# PROC106B_AOP_PWR.net
KiCad netlist of a schematic drawn in Altium Designer
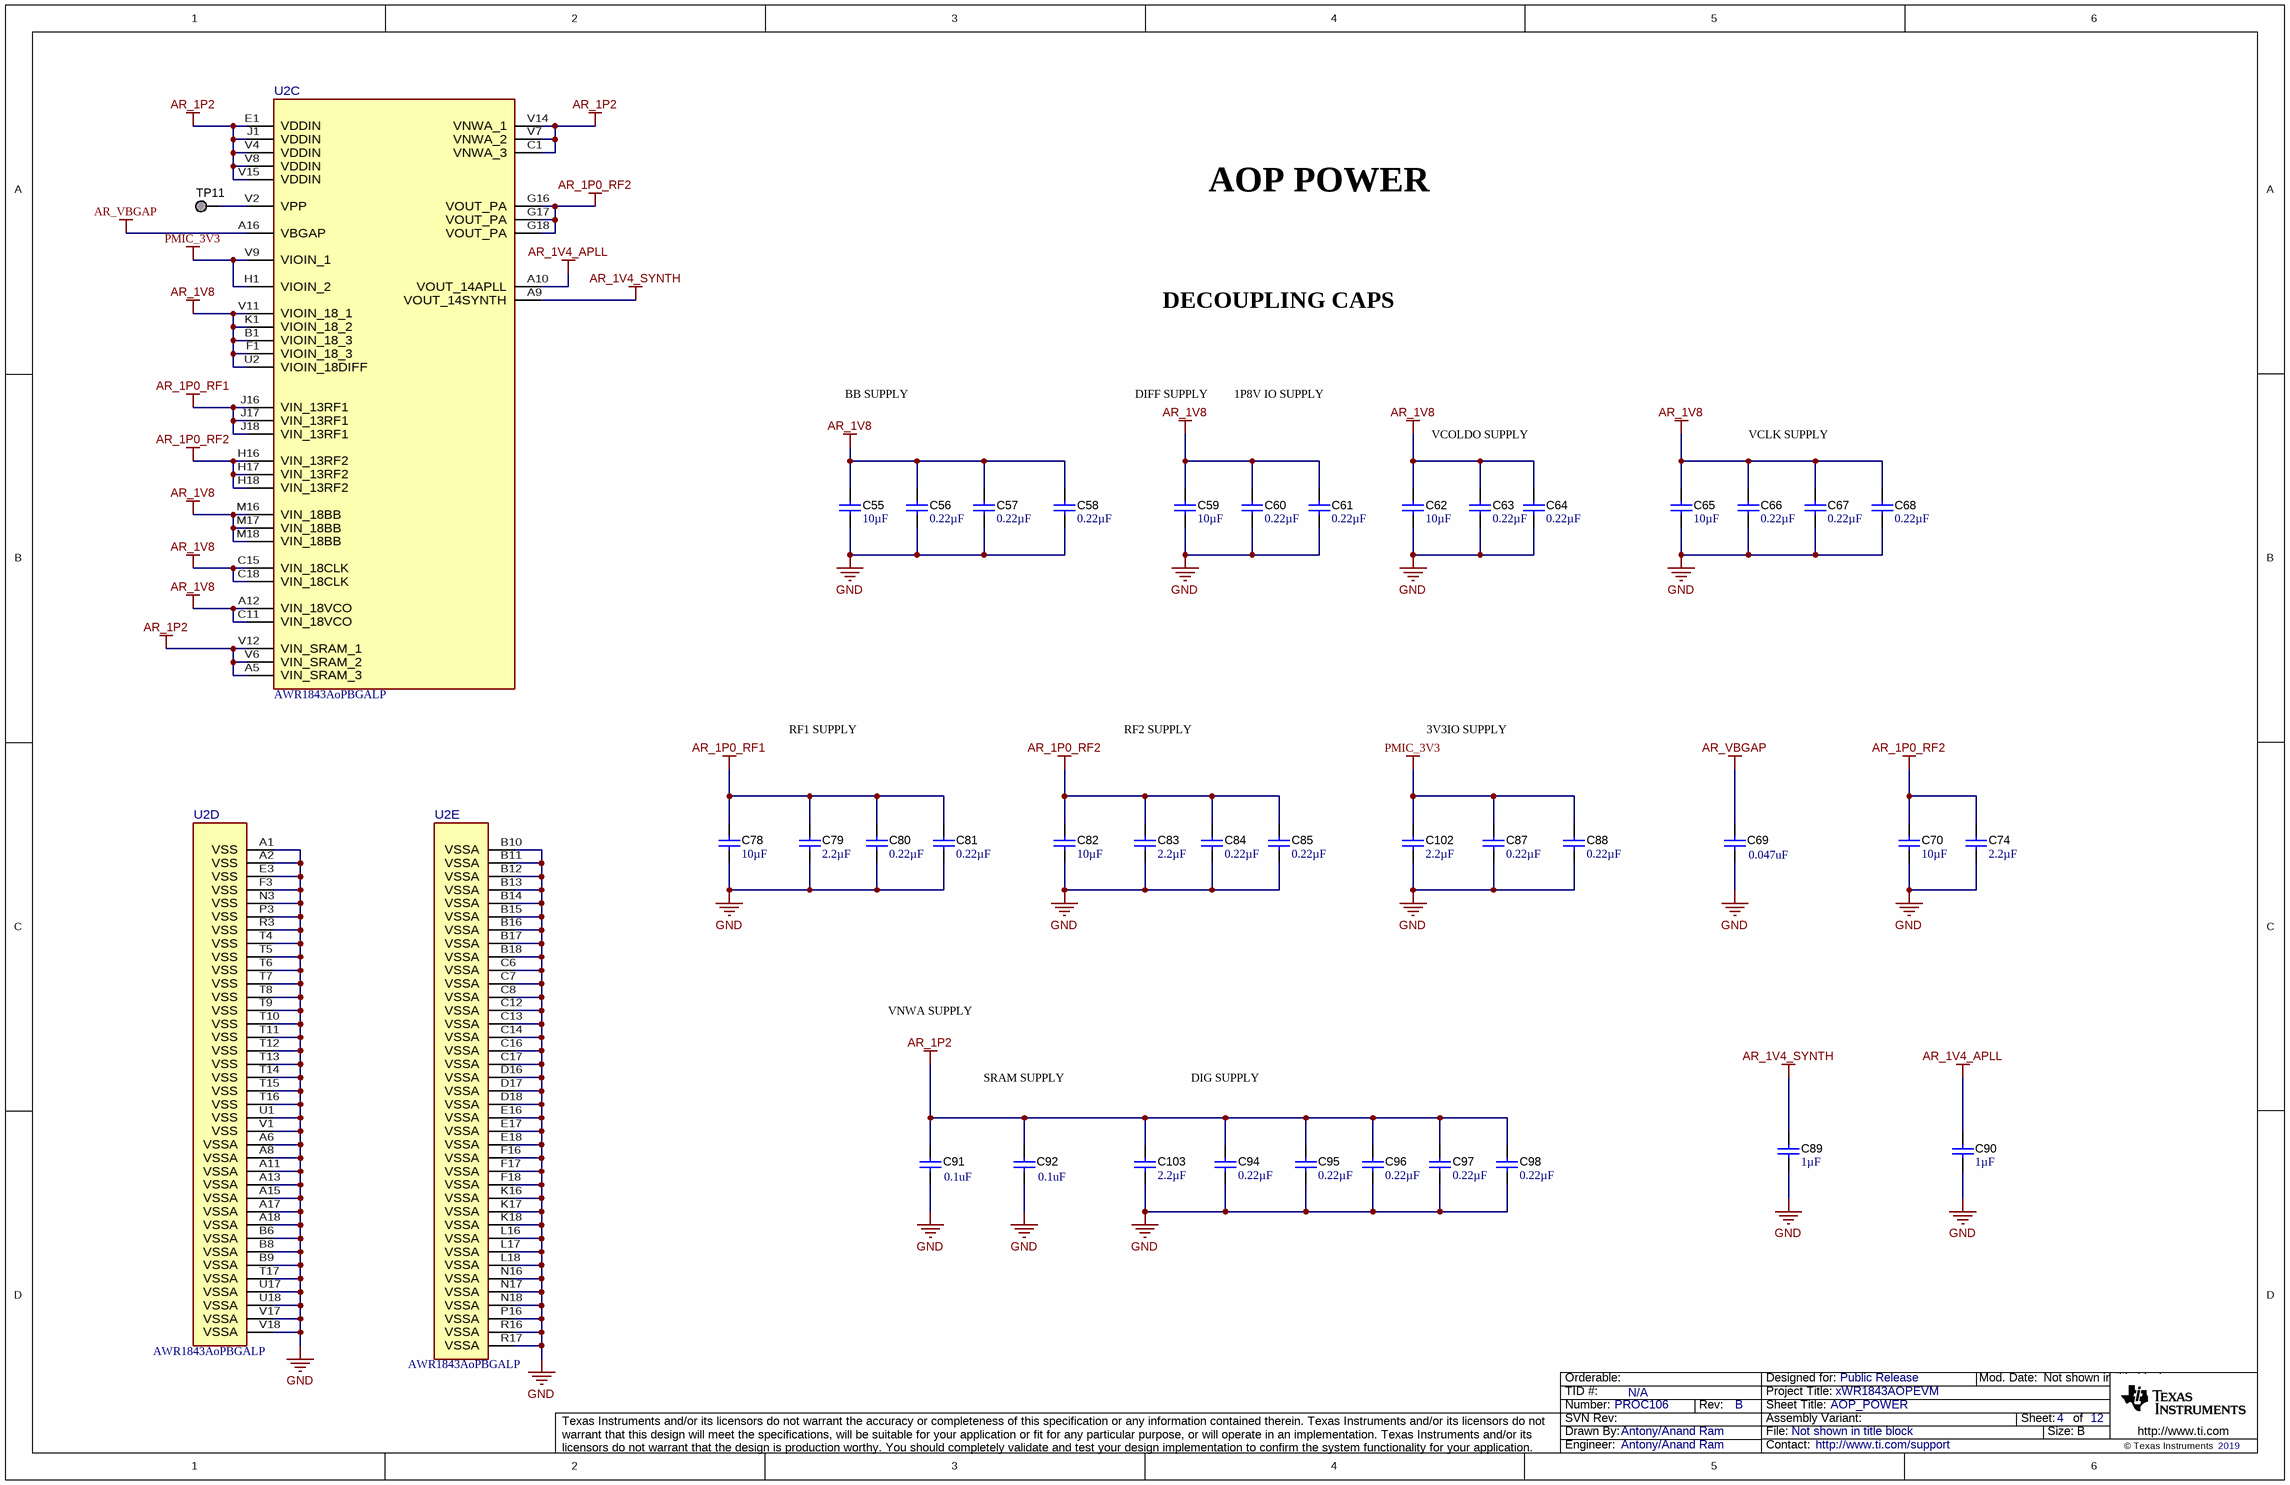
[diagram p0: PROC106B_AOP_PWR.SchDoc]

(export (version "E")
  (design (tool "Eeschema 10.0.6"))
  (components
    (comp (ref "C55")
      (value "GCM21BR71A106KE22L")
      (footprint "0805L")
      (description "CAP, CERM, 10 uF, 10 V, +/- 10%, X7R, 0805")
      (fields
        (field (name "CAP_F") "10µF")
        (field (name "MANUFACTURER") "MuRata")
        (field (name "PUBLISHER") "Texas Instruments")
      )
      (libsource (lib "Altium Vault - TI") (part "Capacitor"))
    )
    (comp (ref "C56")
      (value "GCM155R71C224KE02D")
      (footprint "0402L")
      (description "CAP, CERM, 0.22 µF, 16 V,+/- 10%, X7R, AEC-Q200 Grade 1, 0402")
      (fields (field (name "MANUFACTURER") "MuRata") (field (name "VALUEDISPLAYED") "0.22µF"))
      (libsource (lib "Altium Vault - TI") (part "Capacitor"))
    )
    (comp (ref "C57")
      (value "GCM155R71C224KE02D")
      (footprint "0402L")
      (description "CAP, CERM, 0.22 µF, 16 V,+/- 10%, X7R, AEC-Q200 Grade 1, 0402")
      (fields (field (name "MANUFACTURER") "MuRata") (field (name "VALUEDISPLAYED") "0.22µF"))
      (libsource (lib "Altium Vault - TI") (part "Capacitor"))
    )
    (comp (ref "C58")
      (value "GCM155R71C224KE02D")
      (footprint "0402L")
      (description "CAP, CERM, 0.22 µF, 16 V,+/- 10%, X7R, AEC-Q200 Grade 1, 0402")
      (fields (field (name "MANUFACTURER") "MuRata") (field (name "VALUEDISPLAYED") "0.22µF"))
      (libsource (lib "Altium Vault - TI") (part "Capacitor"))
    )
    (comp (ref "C59")
      (value "GCM21BR71A106KE22L")
      (footprint "0805L")
      (description "CAP, CERM, 10 uF, 10 V, +/- 10%, X7R, 0805")
      (fields
        (field (name "CAP_F") "10µF")
        (field (name "MANUFACTURER") "MuRata")
        (field (name "PUBLISHER") "Texas Instruments")
      )
      (libsource (lib "Altium Vault - TI") (part "Capacitor"))
    )
    (comp (ref "C60")
      (value "GCM155R71C224KE02D")
      (footprint "0402L")
      (description "CAP, CERM, 0.22 µF, 16 V,+/- 10%, X7R, AEC-Q200 Grade 1, 0402")
      (fields (field (name "MANUFACTURER") "MuRata") (field (name "VALUEDISPLAYED") "0.22µF"))
      (libsource (lib "Altium Vault - TI") (part "Capacitor"))
    )
    (comp (ref "C61")
      (value "GCM155R71C224KE02D")
      (footprint "0402L")
      (description "CAP, CERM, 0.22 µF, 16 V,+/- 10%, X7R, AEC-Q200 Grade 1, 0402")
      (fields (field (name "MANUFACTURER") "MuRata") (field (name "VALUEDISPLAYED") "0.22µF"))
      (libsource (lib "Altium Vault - TI") (part "Capacitor"))
    )
    (comp (ref "C62")
      (value "GCM21BR71A106KE22L")
      (footprint "0805L")
      (description "CAP, CERM, 10 uF, 10 V, +/- 10%, X7R, 0805")
      (fields
        (field (name "CAP_F") "10µF")
        (field (name "MANUFACTURER") "MuRata")
        (field (name "PUBLISHER") "Texas Instruments")
      )
      (libsource (lib "Altium Vault - TI") (part "Capacitor"))
    )
    (comp (ref "C63")
      (value "GCM155R71C224KE02D")
      (footprint "0402L")
      (description "CAP, CERM, 0.22 µF, 16 V,+/- 10%, X7R, AEC-Q200 Grade 1, 0402")
      (fields (field (name "MANUFACTURER") "MuRata") (field (name "VALUEDISPLAYED") "0.22µF"))
      (libsource (lib "Altium Vault - TI") (part "Capacitor"))
    )
    (comp (ref "C64")
      (value "GCM155R71C224KE02D")
      (footprint "0402L")
      (description "CAP, CERM, 0.22 µF, 16 V,+/- 10%, X7R, AEC-Q200 Grade 1, 0402")
      (fields (field (name "MANUFACTURER") "MuRata") (field (name "VALUEDISPLAYED") "0.22µF"))
      (libsource (lib "Altium Vault - TI") (part "Capacitor"))
    )
    (comp (ref "C65")
      (value "GCM21BR71A106KE22L")
      (footprint "0805L")
      (description "CAP, CERM, 10 uF, 10 V, +/- 10%, X7R, 0805")
      (fields
        (field (name "CAP_F") "10µF")
        (field (name "MANUFACTURER") "MuRata")
        (field (name "PUBLISHER") "Texas Instruments")
      )
      (libsource (lib "Altium Vault - TI") (part "Capacitor"))
    )
    (comp (ref "C66")
      (value "GCM155R71C224KE02D")
      (footprint "0402L")
      (description "CAP, CERM, 0.22 µF, 16 V,+/- 10%, X7R, AEC-Q200 Grade 1, 0402")
      (fields (field (name "MANUFACTURER") "MuRata") (field (name "VALUEDISPLAYED") "0.22µF"))
      (libsource (lib "Altium Vault - TI") (part "Capacitor"))
    )
    (comp (ref "C67")
      (value "GCM155R71C224KE02D")
      (footprint "0402L")
      (description "CAP, CERM, 0.22 µF, 16 V,+/- 10%, X7R, AEC-Q200 Grade 1, 0402")
      (fields (field (name "MANUFACTURER") "MuRata") (field (name "VALUEDISPLAYED") "0.22µF"))
      (libsource (lib "Altium Vault - TI") (part "Capacitor"))
    )
    (comp (ref "C68")
      (value "GCM155R71C224KE02D")
      (footprint "0402L")
      (description "CAP, CERM, 0.22 µF, 16 V,+/- 10%, X7R, AEC-Q200 Grade 1, 0402")
      (fields (field (name "MANUFACTURER") "MuRata") (field (name "VALUEDISPLAYED") "0.22µF"))
      (libsource (lib "Altium Vault - TI") (part "Capacitor"))
    )
    (comp (ref "C69")
      (value "CGA2B3X7R1H473K050BB")
      (footprint "0402L")
      (description "CAP, CERM, 0.047 uF, 50 V, +/- 10%, X7R, AEC-Q200 Grade 1, 0402")
      (fields
        (field (name "MANUFACTURER") "TDK")
        (field (name "VALUEDISPLAYED") "0.047uF")
        (field (name "PUBLISHER") "Texas Instruments")
      )
      (libsource (lib "Altium Vault - TI") (part "Capacitor"))
    )
    (comp (ref "C70")
      (value "GCM21BR71A106KE22L")
      (footprint "0805L")
      (description "CAP, CERM, 10 uF, 10 V, +/- 10%, X7R, 0805")
      (fields
        (field (name "CAP_F") "10µF")
        (field (name "MANUFACTURER") "MuRata")
        (field (name "PUBLISHER") "Texas Instruments")
      )
      (libsource (lib "Altium Vault - TI") (part "Capacitor"))
    )
    (comp (ref "C74")
      (value "GCM188R70J225KE22D")
      (footprint "0603L")
      (description "CAP, CERM, 2.2 uF, 6.3 V, +/- 10%, X7R, AEC-Q200 Grade 1, 0603")
      (fields
        (field (name "CAP_F") "2.2µF")
        (field (name "MANUFACTURER") "MuRata")
        (field (name "PUBLISHER") "Texas Instruments")
      )
      (libsource (lib "Altium Vault - TI") (part "Capacitor"))
    )
    (comp (ref "C78")
      (value "GCM21BR71A106KE22L")
      (footprint "0805L")
      (description "CAP, CERM, 10 uF, 10 V, +/- 10%, X7R, 0805")
      (fields
        (field (name "CAP_F") "10µF")
        (field (name "MANUFACTURER") "MuRata")
        (field (name "PUBLISHER") "Texas Instruments")
      )
      (libsource (lib "Altium Vault - TI") (part "Capacitor"))
    )
    (comp (ref "C79")
      (value "GCM188R70J225KE22D")
      (footprint "0603L")
      (description "CAP, CERM, 2.2 uF, 6.3 V, +/- 10%, X7R, AEC-Q200 Grade 1, 0603")
      (fields
        (field (name "CAP_F") "2.2µF")
        (field (name "MANUFACTURER") "MuRata")
        (field (name "PUBLISHER") "Texas Instruments")
      )
      (libsource (lib "Altium Vault - TI") (part "Capacitor"))
    )
    (comp (ref "C80")
      (value "GCM155R71C224KE02D")
      (footprint "0402L")
      (description "CAP, CERM, 0.22 µF, 16 V,+/- 10%, X7R, AEC-Q200 Grade 1, 0402")
      (fields (field (name "MANUFACTURER") "MuRata") (field (name "VALUEDISPLAYED") "0.22µF"))
      (libsource (lib "Altium Vault - TI") (part "Capacitor"))
    )
    (comp (ref "C81")
      (value "GCM155R71C224KE02D")
      (footprint "0402L")
      (description "CAP, CERM, 0.22 µF, 16 V,+/- 10%, X7R, AEC-Q200 Grade 1, 0402")
      (fields (field (name "MANUFACTURER") "MuRata") (field (name "VALUEDISPLAYED") "0.22µF"))
      (libsource (lib "Altium Vault - TI") (part "Capacitor"))
    )
    (comp (ref "C82")
      (value "GCM21BR71A106KE22L")
      (footprint "0805L")
      (description "CAP, CERM, 10 uF, 10 V, +/- 10%, X7R, 0805")
      (fields
        (field (name "CAP_F") "10µF")
        (field (name "MANUFACTURER") "MuRata")
        (field (name "PUBLISHER") "Texas Instruments")
      )
      (libsource (lib "Altium Vault - TI") (part "Capacitor"))
    )
    (comp (ref "C83")
      (value "GCM188R70J225KE22D")
      (footprint "0603L")
      (description "CAP, CERM, 2.2 uF, 6.3 V, +/- 10%, X7R, AEC-Q200 Grade 1, 0603")
      (fields
        (field (name "CAP_F") "2.2µF")
        (field (name "MANUFACTURER") "MuRata")
        (field (name "PUBLISHER") "Texas Instruments")
      )
      (libsource (lib "Altium Vault - TI") (part "Capacitor"))
    )
    (comp (ref "C84")
      (value "GCM155R71C224KE02D")
      (footprint "0402L")
      (description "CAP, CERM, 0.22 µF, 16 V,+/- 10%, X7R, AEC-Q200 Grade 1, 0402")
      (fields (field (name "MANUFACTURER") "MuRata") (field (name "VALUEDISPLAYED") "0.22µF"))
      (libsource (lib "Altium Vault - TI") (part "Capacitor"))
    )
    (comp (ref "C85")
      (value "GCM155R71C224KE02D")
      (footprint "0402L")
      (description "CAP, CERM, 0.22 µF, 16 V,+/- 10%, X7R, AEC-Q200 Grade 1, 0402")
      (fields (field (name "MANUFACTURER") "MuRata") (field (name "VALUEDISPLAYED") "0.22µF"))
      (libsource (lib "Altium Vault - TI") (part "Capacitor"))
    )
    (comp (ref "C87")
      (value "GCM155R71C224KE02D")
      (footprint "0402L")
      (description "CAP, CERM, 0.22 µF, 16 V,+/- 10%, X7R, AEC-Q200 Grade 1, 0402")
      (fields (field (name "MANUFACTURER") "MuRata") (field (name "VALUEDISPLAYED") "0.22µF"))
      (libsource (lib "Altium Vault - TI") (part "Capacitor"))
    )
    (comp (ref "C88")
      (value "GCM155R71C224KE02D")
      (footprint "0402L")
      (description "CAP, CERM, 0.22 µF, 16 V,+/- 10%, X7R, AEC-Q200 Grade 1, 0402")
      (fields (field (name "MANUFACTURER") "MuRata") (field (name "VALUEDISPLAYED") "0.22µF"))
      (libsource (lib "Altium Vault - TI") (part "Capacitor"))
    )
    (comp (ref "C89")
      (value "GCM188R71C105KA64D")
      (footprint "0603L")
      (description "CAP, CERM, 1 uF, 16 V, +/- 10%, X7R, AEC-Q200 Grade 1, 0603")
      (fields
        (field (name "MANUFACTURER") "MuRata")
        (field (name "CAP_F") "1µF")
        (field (name "PUBLISHER") "Texas Instruments")
      )
      (libsource (lib "Altium Vault - TI") (part "Capacitor"))
    )
    (comp (ref "C90")
      (value "GCM188R71C105KA64D")
      (footprint "0603L")
      (description "CAP, CERM, 1 uF, 16 V, +/- 10%, X7R, AEC-Q200 Grade 1, 0603")
      (fields
        (field (name "MANUFACTURER") "MuRata")
        (field (name "CAP_F") "1µF")
        (field (name "PUBLISHER") "Texas Instruments")
      )
      (libsource (lib "Altium Vault - TI") (part "Capacitor"))
    )
    (comp (ref "C91")
      (value "GCM155R71C104KA55D")
      (footprint "0402L")
      (description "CAP, CERM, 0.1 uF, 16 V, +/- 10%, X7R, 0402")
      (fields
        (field (name "MANUFACTURER") "MuRata")
        (field (name "VALUEDISPLAYED") "0.1uF")
        (field (name "PUBLISHER") "Texas Instruments")
      )
      (libsource (lib "Altium Vault - TI") (part "Capacitor"))
    )
    (comp (ref "C92")
      (value "GCM155R71C104KA55D")
      (footprint "0402L")
      (description "CAP, CERM, 0.1 uF, 16 V, +/- 10%, X7R, 0402")
      (fields
        (field (name "MANUFACTURER") "MuRata")
        (field (name "VALUEDISPLAYED") "0.1uF")
        (field (name "PUBLISHER") "Texas Instruments")
      )
      (libsource (lib "Altium Vault - TI") (part "Capacitor"))
    )
    (comp (ref "C94")
      (value "GCM155R71C224KE02D")
      (footprint "0402L")
      (description "CAP, CERM, 0.22 µF, 16 V,+/- 10%, X7R, AEC-Q200 Grade 1, 0402")
      (fields (field (name "MANUFACTURER") "MuRata") (field (name "VALUEDISPLAYED") "0.22µF"))
      (libsource (lib "Altium Vault - TI") (part "Capacitor"))
    )
    (comp (ref "C95")
      (value "GCM155R71C224KE02D")
      (footprint "0402L")
      (description "CAP, CERM, 0.22 µF, 16 V,+/- 10%, X7R, AEC-Q200 Grade 1, 0402")
      (fields (field (name "MANUFACTURER") "MuRata") (field (name "VALUEDISPLAYED") "0.22µF"))
      (libsource (lib "Altium Vault - TI") (part "Capacitor"))
    )
    (comp (ref "C96")
      (value "GCM155R71C224KE02D")
      (footprint "0402L")
      (description "CAP, CERM, 0.22 µF, 16 V,+/- 10%, X7R, AEC-Q200 Grade 1, 0402")
      (fields (field (name "MANUFACTURER") "MuRata") (field (name "VALUEDISPLAYED") "0.22µF"))
      (libsource (lib "Altium Vault - TI") (part "Capacitor"))
    )
    (comp (ref "C97")
      (value "GCM155R71C224KE02D")
      (footprint "0402L")
      (description "CAP, CERM, 0.22 µF, 16 V,+/- 10%, X7R, AEC-Q200 Grade 1, 0402")
      (fields (field (name "MANUFACTURER") "MuRata") (field (name "VALUEDISPLAYED") "0.22µF"))
      (libsource (lib "Altium Vault - TI") (part "Capacitor"))
    )
    (comp (ref "C98")
      (value "GCM155R71C224KE02D")
      (footprint "0402L")
      (description "CAP, CERM, 0.22 µF, 16 V,+/- 10%, X7R, AEC-Q200 Grade 1, 0402")
      (fields (field (name "MANUFACTURER") "MuRata") (field (name "VALUEDISPLAYED") "0.22µF"))
      (libsource (lib "Altium Vault - TI") (part "Capacitor"))
    )
    (comp (ref "C102")
      (value "GCM188R70J225KE22D")
      (footprint "0603L")
      (description "CAP, CERM, 2.2 uF, 6.3 V, +/- 10%, X7R, AEC-Q200 Grade 1, 0603")
      (fields
        (field (name "CAP_F") "2.2µF")
        (field (name "MANUFACTURER") "MuRata")
        (field (name "PUBLISHER") "Texas Instruments")
      )
      (libsource (lib "Altium Vault - TI") (part "Capacitor"))
    )
    (comp (ref "C103")
      (value "GCM188R70J225KE22D")
      (footprint "0603L")
      (description "CAP, CERM, 2.2 uF, 6.3 V, +/- 10%, X7R, AEC-Q200 Grade 1, 0603")
      (fields
        (field (name "CAP_F") "2.2µF")
        (field (name "MANUFACTURER") "MuRata")
        (field (name "PUBLISHER") "Texas Instruments")
      )
      (libsource (lib "Altium Vault - TI") (part "Capacitor"))
    )
    (comp (ref "TP11")
      (value "TP_SM_1MM")
      (footprint "TP_SM_1MM")
      (description "1mm Test Point, SMT")
      (fields (field (name "MANUFACTURER") "Any") (field (name "PUBLISHER") "Texas Instruments"))
      (libsource (lib "Altium Vault - TI") (part "TESTPOINT"))
    )
    (comp (ref "U2")
      (value "AWR1843AoPBGALP")
      (footprint "ALP0180A-MFG")
      (fields (field (name "MANUFACTURER") "Texas Instruments") (field (name "PARTNUMBER") "AWR1843AoPBGALP"))
      (libsource (lib "Altium Vault - TI") (part "SYM-AWR1843AoPBGALP"))
    )
  )
  (nets
    (net (code "1") (name "AR_1P0_RF1") (class "Default")
      (node (ref "C78") (pin "1") (pinfunction "1_1") (pintype "passive"))
      (node (ref "C79") (pin "1") (pinfunction "1_1") (pintype "passive"))
      (node (ref "C80") (pin "1") (pinfunction "1_1") (pintype "passive"))
      (node (ref "C81") (pin "1") (pinfunction "1_1") (pintype "passive"))
      (node (ref "U2") (pin "J16") (pinfunction "VIN_13RF1_J16") (pintype "power_in"))
      (node (ref "U2") (pin "J17") (pinfunction "VIN_13RF1_J17") (pintype "power_in"))
      (node (ref "U2") (pin "J18") (pinfunction "VIN_13RF1_J18") (pintype "power_in"))
    )
    (net (code "2") (name "AR_1P0_RF2") (class "Default")
      (node (ref "C70") (pin "1") (pinfunction "1_1") (pintype "passive"))
      (node (ref "C74") (pin "1") (pinfunction "1_1") (pintype "passive"))
      (node (ref "C82") (pin "1") (pinfunction "1_1") (pintype "passive"))
      (node (ref "C83") (pin "1") (pinfunction "1_1") (pintype "passive"))
      (node (ref "C84") (pin "1") (pinfunction "1_1") (pintype "passive"))
      (node (ref "C85") (pin "1") (pinfunction "1_1") (pintype "passive"))
      (node (ref "U2") (pin "G16") (pinfunction "VOUT_PA_G16") (pintype "passive"))
      (node (ref "U2") (pin "G17") (pinfunction "VOUT_PA_G17") (pintype "passive"))
      (node (ref "U2") (pin "G18") (pinfunction "VOUT_PA_G18") (pintype "passive"))
      (node (ref "U2") (pin "H16") (pinfunction "VIN_13RF2_H16") (pintype "power_in"))
      (node (ref "U2") (pin "H17") (pinfunction "VIN_13RF2_H17") (pintype "power_in"))
      (node (ref "U2") (pin "H18") (pinfunction "VIN_13RF2_H18") (pintype "power_in"))
    )
    (net (code "3") (name "AR_1P2") (class "Default")
      (node (ref "C103") (pin "1") (pinfunction "1_1") (pintype "passive"))
      (node (ref "C91") (pin "2") (pinfunction "2_2") (pintype "passive"))
      (node (ref "C92") (pin "2") (pinfunction "2_2") (pintype "passive"))
      (node (ref "C94") (pin "1") (pinfunction "1_1") (pintype "passive"))
      (node (ref "C95") (pin "1") (pinfunction "1_1") (pintype "passive"))
      (node (ref "C96") (pin "1") (pinfunction "1_1") (pintype "passive"))
      (node (ref "C97") (pin "1") (pinfunction "1_1") (pintype "passive"))
      (node (ref "C98") (pin "1") (pinfunction "1_1") (pintype "passive"))
      (node (ref "U2") (pin "A5") (pinfunction "VIN_SRAM_3_A5") (pintype "power_in"))
      (node (ref "U2") (pin "C1") (pinfunction "VNWA_3_C1") (pintype "power_in"))
      (node (ref "U2") (pin "E1") (pinfunction "VDDIN_E1") (pintype "power_in"))
      (node (ref "U2") (pin "J1") (pinfunction "VDDIN_J1") (pintype "power_in"))
      (node (ref "U2") (pin "V12") (pinfunction "VIN_SRAM_1_V12") (pintype "power_in"))
      (node (ref "U2") (pin "V14") (pinfunction "VNWA_1_V14") (pintype "power_in"))
      (node (ref "U2") (pin "V15") (pinfunction "VDDIN_V15") (pintype "power_in"))
      (node (ref "U2") (pin "V4") (pinfunction "VDDIN_V4") (pintype "power_in"))
      (node (ref "U2") (pin "V6") (pinfunction "VIN_SRAM_2_V6") (pintype "power_in"))
      (node (ref "U2") (pin "V7") (pinfunction "VNWA_2_V7") (pintype "power_in"))
      (node (ref "U2") (pin "V8") (pinfunction "VDDIN_V8") (pintype "power_in"))
    )
    (net (code "4") (name "AR_1V4_APLL") (class "Default")
      (node (ref "C90") (pin "1") (pinfunction "1_1") (pintype "passive"))
      (node (ref "U2") (pin "A10") (pinfunction "VOUT_14APLL_A10") (pintype "passive"))
    )
    (net (code "5") (name "AR_1V4_SYNTH") (class "Default")
      (node (ref "C89") (pin "1") (pinfunction "1_1") (pintype "passive"))
      (node (ref "U2") (pin "A9") (pinfunction "VOUT_14SYNTH_A9") (pintype "passive"))
    )
    (net (code "6") (name "AR_1V8") (class "Default")
      (node (ref "C55") (pin "1") (pinfunction "1_1") (pintype "passive"))
      (node (ref "C56") (pin "1") (pinfunction "1_1") (pintype "passive"))
      (node (ref "C57") (pin "1") (pinfunction "1_1") (pintype "passive"))
      (node (ref "C58") (pin "1") (pinfunction "1_1") (pintype "passive"))
      (node (ref "C59") (pin "1") (pinfunction "1_1") (pintype "passive"))
      (node (ref "C60") (pin "1") (pinfunction "1_1") (pintype "passive"))
      (node (ref "C61") (pin "1") (pinfunction "1_1") (pintype "passive"))
      (node (ref "C62") (pin "1") (pinfunction "1_1") (pintype "passive"))
      (node (ref "C63") (pin "1") (pinfunction "1_1") (pintype "passive"))
      (node (ref "C64") (pin "1") (pinfunction "1_1") (pintype "passive"))
      (node (ref "C65") (pin "1") (pinfunction "1_1") (pintype "passive"))
      (node (ref "C66") (pin "1") (pinfunction "1_1") (pintype "passive"))
      (node (ref "C67") (pin "1") (pinfunction "1_1") (pintype "passive"))
      (node (ref "C68") (pin "1") (pinfunction "1_1") (pintype "passive"))
      (node (ref "U2") (pin "A12") (pinfunction "VIN_18VCO_A12") (pintype "power_in"))
      (node (ref "U2") (pin "B1") (pinfunction "VIOIN_18_3_B1") (pintype "power_in"))
      (node (ref "U2") (pin "C11") (pinfunction "VIN_18VCO_C11") (pintype "power_in"))
      (node (ref "U2") (pin "C15") (pinfunction "VIN_18CLK_C15") (pintype "power_in"))
      (node (ref "U2") (pin "C18") (pinfunction "VIN_18CLK_C18") (pintype "power_in"))
      (node (ref "U2") (pin "F1") (pinfunction "VIOIN_18_3_F1") (pintype "power_in"))
      (node (ref "U2") (pin "K1") (pinfunction "VIOIN_18_2_K1") (pintype "power_in"))
      (node (ref "U2") (pin "M16") (pinfunction "VIN_18BB_M16") (pintype "power_in"))
      (node (ref "U2") (pin "M17") (pinfunction "VIN_18BB_M17") (pintype "power_in"))
      (node (ref "U2") (pin "M18") (pinfunction "VIN_18BB_M18") (pintype "power_in"))
      (node (ref "U2") (pin "U2") (pinfunction "VIOIN_18DIFF_U2") (pintype "power_in"))
      (node (ref "U2") (pin "V11") (pinfunction "VIOIN_18_1_V11") (pintype "power_in"))
    )
    (net (code "7") (name "AR_VBGAP") (class "Default")
      (node (ref "C69") (pin "1") (pinfunction "1_1") (pintype "passive"))
      (node (ref "U2") (pin "A16") (pinfunction "VBGAP_A16") (pintype "power_in"))
    )
    (net (code "8") (name "GND") (class "Default")
      (node (ref "C102") (pin "2") (pinfunction "2_2") (pintype "passive"))
      (node (ref "C103") (pin "2") (pinfunction "2_2") (pintype "passive"))
      (node (ref "C55") (pin "2") (pinfunction "2_2") (pintype "passive"))
      (node (ref "C56") (pin "2") (pinfunction "2_2") (pintype "passive"))
      (node (ref "C57") (pin "2") (pinfunction "2_2") (pintype "passive"))
      (node (ref "C58") (pin "2") (pinfunction "2_2") (pintype "passive"))
      (node (ref "C59") (pin "2") (pinfunction "2_2") (pintype "passive"))
      (node (ref "C60") (pin "2") (pinfunction "2_2") (pintype "passive"))
      (node (ref "C61") (pin "2") (pinfunction "2_2") (pintype "passive"))
      (node (ref "C62") (pin "2") (pinfunction "2_2") (pintype "passive"))
      (node (ref "C63") (pin "2") (pinfunction "2_2") (pintype "passive"))
      (node (ref "C64") (pin "2") (pinfunction "2_2") (pintype "passive"))
      (node (ref "C65") (pin "2") (pinfunction "2_2") (pintype "passive"))
      (node (ref "C66") (pin "2") (pinfunction "2_2") (pintype "passive"))
      (node (ref "C67") (pin "2") (pinfunction "2_2") (pintype "passive"))
      (node (ref "C68") (pin "2") (pinfunction "2_2") (pintype "passive"))
      (node (ref "C69") (pin "2") (pinfunction "2_2") (pintype "passive"))
      (node (ref "C70") (pin "2") (pinfunction "2_2") (pintype "passive"))
      (node (ref "C74") (pin "2") (pinfunction "2_2") (pintype "passive"))
      (node (ref "C78") (pin "2") (pinfunction "2_2") (pintype "passive"))
      (node (ref "C79") (pin "2") (pinfunction "2_2") (pintype "passive"))
      (node (ref "C80") (pin "2") (pinfunction "2_2") (pintype "passive"))
      (node (ref "C81") (pin "2") (pinfunction "2_2") (pintype "passive"))
      (node (ref "C82") (pin "2") (pinfunction "2_2") (pintype "passive"))
      (node (ref "C83") (pin "2") (pinfunction "2_2") (pintype "passive"))
      (node (ref "C84") (pin "2") (pinfunction "2_2") (pintype "passive"))
      (node (ref "C85") (pin "2") (pinfunction "2_2") (pintype "passive"))
      (node (ref "C87") (pin "2") (pinfunction "2_2") (pintype "passive"))
      (node (ref "C88") (pin "2") (pinfunction "2_2") (pintype "passive"))
      (node (ref "C89") (pin "2") (pinfunction "2_2") (pintype "passive"))
      (node (ref "C90") (pin "2") (pinfunction "2_2") (pintype "passive"))
      (node (ref "C91") (pin "1") (pinfunction "1_1") (pintype "passive"))
      (node (ref "C92") (pin "1") (pinfunction "1_1") (pintype "passive"))
      (node (ref "C94") (pin "2") (pinfunction "2_2") (pintype "passive"))
      (node (ref "C95") (pin "2") (pinfunction "2_2") (pintype "passive"))
      (node (ref "C96") (pin "2") (pinfunction "2_2") (pintype "passive"))
      (node (ref "C97") (pin "2") (pinfunction "2_2") (pintype "passive"))
      (node (ref "C98") (pin "2") (pinfunction "2_2") (pintype "passive"))
      (node (ref "U2") (pin "A1") (pinfunction "VSS_A1") (pintype "power_in"))
      (node (ref "U2") (pin "A11") (pinfunction "VSSA_A11") (pintype "power_in"))
      (node (ref "U2") (pin "A13") (pinfunction "VSSA_A13") (pintype "power_in"))
      (node (ref "U2") (pin "A15") (pinfunction "VSSA_A15") (pintype "power_in"))
      (node (ref "U2") (pin "A17") (pinfunction "VSSA_A17") (pintype "power_in"))
      (node (ref "U2") (pin "A18") (pinfunction "VSSA_A18") (pintype "power_in"))
      (node (ref "U2") (pin "A2") (pinfunction "VSS_A2") (pintype "power_in"))
      (node (ref "U2") (pin "A6") (pinfunction "VSSA_A6") (pintype "power_in"))
      (node (ref "U2") (pin "A8") (pinfunction "VSSA_A8") (pintype "power_in"))
      (node (ref "U2") (pin "B10") (pinfunction "VSSA_B10") (pintype "power_in"))
      (node (ref "U2") (pin "B11") (pinfunction "VSSA_B11") (pintype "power_in"))
      (node (ref "U2") (pin "B12") (pinfunction "VSSA_B12") (pintype "power_in"))
      (node (ref "U2") (pin "B13") (pinfunction "VSSA_B13") (pintype "power_in"))
      (node (ref "U2") (pin "B14") (pinfunction "VSSA_B14") (pintype "power_in"))
      (node (ref "U2") (pin "B15") (pinfunction "VSSA_B15") (pintype "power_in"))
      (node (ref "U2") (pin "B16") (pinfunction "VSSA_B16") (pintype "power_in"))
      (node (ref "U2") (pin "B17") (pinfunction "VSSA_B17") (pintype "power_in"))
      (node (ref "U2") (pin "B18") (pinfunction "VSSA_B18") (pintype "power_in"))
      (node (ref "U2") (pin "B6") (pinfunction "VSSA_B6") (pintype "power_in"))
      (node (ref "U2") (pin "B8") (pinfunction "VSSA_B8") (pintype "power_in"))
      (node (ref "U2") (pin "B9") (pinfunction "VSSA_B9") (pintype "power_in"))
      (node (ref "U2") (pin "C12") (pinfunction "VSSA_C12") (pintype "power_in"))
      (node (ref "U2") (pin "C13") (pinfunction "VSSA_C13") (pintype "power_in"))
      (node (ref "U2") (pin "C14") (pinfunction "VSSA_C14") (pintype "power_in"))
      (node (ref "U2") (pin "C16") (pinfunction "VSSA_C16") (pintype "power_in"))
      (node (ref "U2") (pin "C17") (pinfunction "VSSA_C17") (pintype "power_in"))
      (node (ref "U2") (pin "C6") (pinfunction "VSSA_C6") (pintype "power_in"))
      (node (ref "U2") (pin "C7") (pinfunction "VSSA_C7") (pintype "power_in"))
      (node (ref "U2") (pin "C8") (pinfunction "VSSA_C8") (pintype "power_in"))
      (node (ref "U2") (pin "D16") (pinfunction "VSSA_D16") (pintype "power_in"))
      (node (ref "U2") (pin "D17") (pinfunction "VSSA_D17") (pintype "power_in"))
      (node (ref "U2") (pin "D18") (pinfunction "VSSA_D18") (pintype "power_in"))
      (node (ref "U2") (pin "E16") (pinfunction "VSSA_E16") (pintype "power_in"))
      (node (ref "U2") (pin "E17") (pinfunction "VSSA_E17") (pintype "power_in"))
      (node (ref "U2") (pin "E18") (pinfunction "VSSA_E18") (pintype "power_in"))
      (node (ref "U2") (pin "E3") (pinfunction "VSS_E3") (pintype "power_in"))
      (node (ref "U2") (pin "F16") (pinfunction "VSSA_F16") (pintype "power_in"))
      (node (ref "U2") (pin "F17") (pinfunction "VSSA_F17") (pintype "power_in"))
      (node (ref "U2") (pin "F18") (pinfunction "VSSA_F18") (pintype "power_in"))
      (node (ref "U2") (pin "F3") (pinfunction "VSS_F3") (pintype "power_in"))
      (node (ref "U2") (pin "K16") (pinfunction "VSSA_K16") (pintype "power_in"))
      (node (ref "U2") (pin "K17") (pinfunction "VSSA_K17") (pintype "power_in"))
      (node (ref "U2") (pin "K18") (pinfunction "VSSA_K18") (pintype "power_in"))
      (node (ref "U2") (pin "L16") (pinfunction "VSSA_L16") (pintype "power_in"))
      (node (ref "U2") (pin "L17") (pinfunction "VSSA_L17") (pintype "power_in"))
      (node (ref "U2") (pin "L18") (pinfunction "VSSA_L18") (pintype "power_in"))
      (node (ref "U2") (pin "N16") (pinfunction "VSSA_N16") (pintype "power_in"))
      (node (ref "U2") (pin "N17") (pinfunction "VSSA_N17") (pintype "power_in"))
      (node (ref "U2") (pin "N18") (pinfunction "VSSA_N18") (pintype "power_in"))
      (node (ref "U2") (pin "N3") (pinfunction "VSS_N3") (pintype "power_in"))
      (node (ref "U2") (pin "P16") (pinfunction "VSSA_P16") (pintype "power_in"))
      (node (ref "U2") (pin "P3") (pinfunction "VSS_P3") (pintype "power_in"))
      (node (ref "U2") (pin "R16") (pinfunction "VSSA_R16") (pintype "power_in"))
      (node (ref "U2") (pin "R17") (pinfunction "VSSA_R17") (pintype "power_in"))
      (node (ref "U2") (pin "R3") (pinfunction "VSS_R3") (pintype "power_in"))
      (node (ref "U2") (pin "T10") (pinfunction "VSS_T10") (pintype "power_in"))
      (node (ref "U2") (pin "T11") (pinfunction "VSS_T11") (pintype "power_in"))
      (node (ref "U2") (pin "T12") (pinfunction "VSS_T12") (pintype "power_in"))
      (node (ref "U2") (pin "T13") (pinfunction "VSS_T13") (pintype "power_in"))
      (node (ref "U2") (pin "T14") (pinfunction "VSS_T14") (pintype "power_in"))
      (node (ref "U2") (pin "T15") (pinfunction "VSS_T15") (pintype "power_in"))
      (node (ref "U2") (pin "T16") (pinfunction "VSS_T16") (pintype "power_in"))
      (node (ref "U2") (pin "T17") (pinfunction "VSSA_T17") (pintype "power_in"))
      (node (ref "U2") (pin "T4") (pinfunction "VSS_T4") (pintype "power_in"))
      (node (ref "U2") (pin "T5") (pinfunction "VSS_T5") (pintype "power_in"))
      (node (ref "U2") (pin "T6") (pinfunction "VSS_T6") (pintype "power_in"))
      (node (ref "U2") (pin "T7") (pinfunction "VSS_T7") (pintype "power_in"))
      (node (ref "U2") (pin "T8") (pinfunction "VSS_T8") (pintype "power_in"))
      (node (ref "U2") (pin "T9") (pinfunction "VSS_T9") (pintype "power_in"))
      (node (ref "U2") (pin "U1") (pinfunction "VSS_U1") (pintype "power_in"))
      (node (ref "U2") (pin "U17") (pinfunction "VSSA_U17") (pintype "power_in"))
      (node (ref "U2") (pin "U18") (pinfunction "VSSA_U18") (pintype "power_in"))
      (node (ref "U2") (pin "V1") (pinfunction "VSS_V1") (pintype "power_in"))
      (node (ref "U2") (pin "V17") (pinfunction "VSSA_V17") (pintype "power_in"))
      (node (ref "U2") (pin "V18") (pinfunction "VSSA_V18") (pintype "power_in"))
    )
    (net (code "9") (name "Net-(U2C-VPP)") (class "Default")
      (node (ref "TP11") (pin "1") (pintype "passive"))
      (node (ref "U2") (pin "V2") (pinfunction "VPP_V2") (pintype "power_in"))
    )
    (net (code "10") (name "PMIC_3V3") (class "Default")
      (node (ref "C102") (pin "1") (pinfunction "1_1") (pintype "passive"))
      (node (ref "C87") (pin "1") (pinfunction "1_1") (pintype "passive"))
      (node (ref "C88") (pin "1") (pinfunction "1_1") (pintype "passive"))
      (node (ref "U2") (pin "H1") (pinfunction "VIOIN_2_H1") (pintype "power_in"))
      (node (ref "U2") (pin "V9") (pinfunction "VIOIN_1_V9") (pintype "power_in"))
    )
  )
)
